# AD7190.net
KiCad netlist of a schematic drawn in Altium Designer
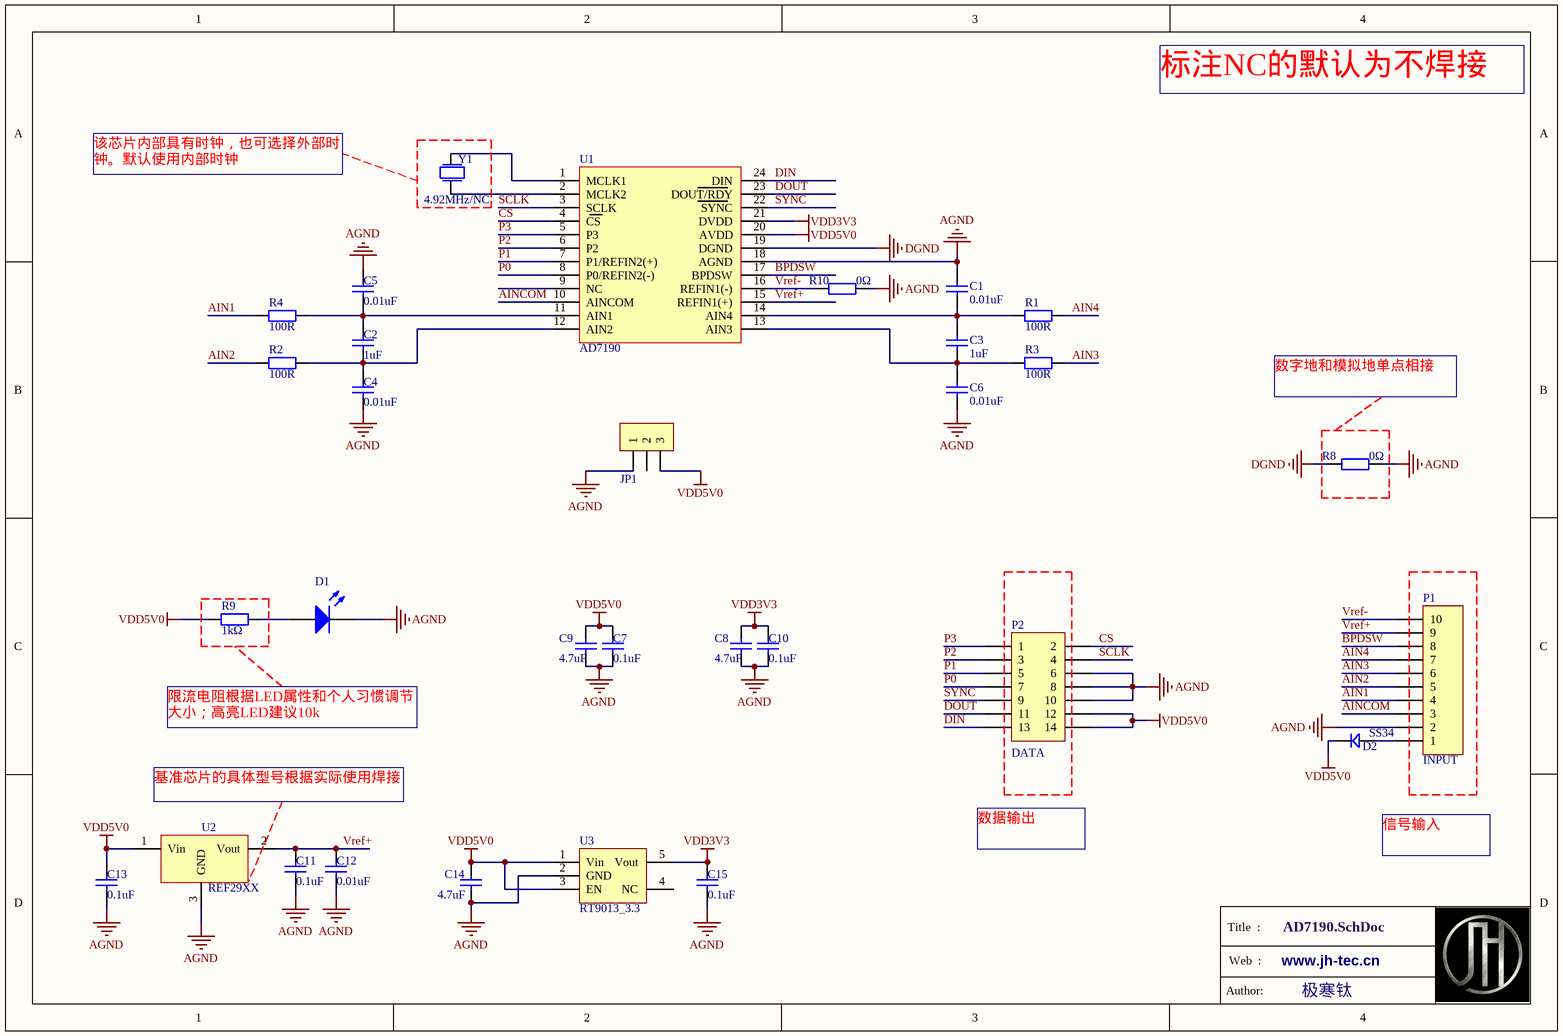
[diagram p0: AD7190.SchDoc]

(export (version "E")
  (design (tool "Eeschema 10.0.6"))
  (components
    (comp (ref "C1")
      (value "0.01uF")
      (footprint "JH_PCB:C0603")
      (description "Capacitor (Semiconductor SIM Model)")
      (fields (field (name "PUBLISHER") "Altium Limited"))
      (libsource (lib "mylib") (part "Cap Semi"))
    )
    (comp (ref "C2")
      (value "1uF")
      (footprint "JH_PCB:C0603")
      (description "Capacitor (Semiconductor SIM Model)")
      (fields (field (name "PUBLISHER") "Altium Limited"))
      (libsource (lib "mylib") (part "Cap Semi"))
    )
    (comp (ref "C3")
      (value "1uF")
      (footprint "JH_PCB:C0603")
      (description "Capacitor (Semiconductor SIM Model)")
      (fields (field (name "PUBLISHER") "Altium Limited"))
      (libsource (lib "mylib") (part "Cap Semi"))
    )
    (comp (ref "C4")
      (value "0.01uF")
      (footprint "JH_PCB:C0603")
      (description "Capacitor (Semiconductor SIM Model)")
      (fields (field (name "PUBLISHER") "Altium Limited"))
      (libsource (lib "mylib") (part "Cap Semi"))
    )
    (comp (ref "C5")
      (value "0.01uF")
      (footprint "JH_PCB:C0603")
      (description "Capacitor (Semiconductor SIM Model)")
      (fields (field (name "PUBLISHER") "Altium Limited"))
      (libsource (lib "mylib") (part "Cap Semi"))
    )
    (comp (ref "C6")
      (value "0.01uF")
      (footprint "JH_PCB:C0603")
      (description "Capacitor (Semiconductor SIM Model)")
      (fields (field (name "PUBLISHER") "Altium Limited"))
      (libsource (lib "mylib") (part "Cap Semi"))
    )
    (comp (ref "C7")
      (value "0.1uF")
      (footprint "JH_PCB:C0603")
      (description "Capacitor (Semiconductor SIM Model)")
      (fields (field (name "PUBLISHER") "Altium Limited"))
      (libsource (lib "mylib") (part "Cap Semi"))
    )
    (comp (ref "C8")
      (value "4.7uF")
      (footprint "JH_PCB:C0805")
      (description "Capacitor (Semiconductor SIM Model)")
      (fields (field (name "PUBLISHER") "Altium Limited"))
      (libsource (lib "mylib") (part "Cap Semi"))
    )
    (comp (ref "C9")
      (value "4.7uF")
      (footprint "JH_PCB:C0805")
      (description "Capacitor (Semiconductor SIM Model)")
      (fields (field (name "PUBLISHER") "Altium Limited"))
      (libsource (lib "mylib") (part "Cap Semi"))
    )
    (comp (ref "C10")
      (value "0.1uF")
      (footprint "JH_PCB:C0603")
      (description "Capacitor (Semiconductor SIM Model)")
      (fields (field (name "PUBLISHER") "Altium Limited"))
      (libsource (lib "mylib") (part "Cap Semi"))
    )
    (comp (ref "C11")
      (value "0.1uF")
      (footprint "JH_PCB:C0603")
      (description "Capacitor (Semiconductor SIM Model)")
      (fields (field (name "PUBLISHER") "Altium Limited"))
      (libsource (lib "mylib") (part "Cap Semi"))
    )
    (comp (ref "C12")
      (value "0.01uF")
      (footprint "JH_PCB:C0603")
      (description "Capacitor (Semiconductor SIM Model)")
      (fields (field (name "PUBLISHER") "Altium Limited"))
      (libsource (lib "mylib") (part "Cap Semi"))
    )
    (comp (ref "C13")
      (value "0.1uF")
      (footprint "JH_PCB:C0603")
      (description "Capacitor (Semiconductor SIM Model)")
      (fields (field (name "PUBLISHER") "Altium Limited"))
      (libsource (lib "mylib") (part "Cap Semi"))
    )
    (comp (ref "C14")
      (value "4.7uF")
      (footprint "JH_PCB:C0805")
      (description "Capacitor (Semiconductor SIM Model)")
      (fields (field (name "PUBLISHER") "Altium Limited"))
      (libsource (lib "mylib") (part "Cap Semi"))
    )
    (comp (ref "C15")
      (value "0.1uF")
      (footprint "JH_PCB:C0603")
      (description "Capacitor (Semiconductor SIM Model)")
      (fields (field (name "PUBLISHER") "Altium Limited"))
      (libsource (lib "mylib") (part "Cap Semi"))
    )
    (comp (ref "D1")
      (value "LED3")
      (footprint "JH_PCB:LED_GREEN_0603")
      (description "Typical BLUE SiC LED")
      (fields (field (name "PUBLISHER") "Altium Limited"))
      (libsource (lib "mylib") (part "LED3"))
    )
    (comp (ref "D2")
      (value "SS34")
      (footprint "JH_PCB:DO-214AC")
      (description "1N4148")
      (libsource (lib "ATK-SIM900A") (part "D"))
    )
    (comp (ref "JP1")
      (value "HDR-1X3")
      (footprint "XH2.54-WI-3P")
      (description "3P接插件")
      (libsource (lib "XH2.54") (part "Header 3"))
    )
    (comp (ref "P1")
      (value "INPUT")
      (footprint "JH_PCB:KF2EDGK-3.81-10P")
      (description "Header, 10-Pin")
      (fields (field (name "PUBLISHER") "Altium Limited"))
      (libsource (lib "Miscellaneous Connectors") (part "Header 10"))
    )
    (comp (ref "P2")
      (value "DATA")
      (footprint "JH_PCB:HDR2X7")
      (description "Header, 7-Pin, Dual row")
      (fields (field (name "PUBLISHER") "Altium Limited"))
      (libsource (lib "Miscellaneous Connectors") (part "Header 7X2"))
    )
    (comp (ref "R1")
      (value "100R")
      (footprint "JH_PCB:R0603")
      (description "Resistor")
      (fields (field (name "PUBLISHER") "Altium Limited"))
      (libsource (lib "Miscellaneous Devices") (part "Res2"))
    )
    (comp (ref "R2")
      (value "100R")
      (footprint "JH_PCB:R0603")
      (description "Resistor")
      (fields (field (name "PUBLISHER") "Altium Limited"))
      (libsource (lib "") (part "Res2_2"))
    )
    (comp (ref "R3")
      (value "100R")
      (footprint "JH_PCB:R0603")
      (description "Resistor")
      (fields (field (name "PUBLISHER") "Altium Limited"))
      (libsource (lib "Miscellaneous Devices") (part "Res2"))
    )
    (comp (ref "R4")
      (value "100R")
      (footprint "JH_PCB:R0603")
      (description "Resistor")
      (fields (field (name "PUBLISHER") "Altium Limited"))
      (libsource (lib "") (part "Res2_2"))
    )
    (comp (ref "R8")
      (value "0Ω")
      (footprint "JH_PCB:R0603")
      (description "Resistor")
      (fields (field (name "PUBLISHER") "Altium Limited"))
      (libsource (lib "") (part "Res2_1"))
    )
    (comp (ref "R9")
      (value "1kΩ")
      (footprint "JH_PCB:R0603")
      (description "Resistor")
      (fields (field (name "PUBLISHER") "Altium Limited"))
      (libsource (lib "") (part "Res2_1"))
    )
    (comp (ref "R10")
      (value "0Ω")
      (footprint "JH_PCB:R0603")
      (description "Resistor")
      (fields (field (name "PUBLISHER") "Altium Limited"))
      (libsource (lib "") (part "Res2_1"))
    )
    (comp (ref "U1") (value "AD7190") (footprint "JH_PCB:TSSOP24") (libsource (lib "常用sch") (part "AD7190")))
    (comp (ref "U2") (value "REF29XX") (libsource (lib "常用sch") (part "REF29XX")))
    (comp (ref "U3")
      (value "RT9013_3.3")
      (footprint "SOT23-5")
      (description "LDO")
      (libsource (lib "Black") (part "RT9013"))
    )
    (comp (ref "Y1")
      (value "4.92MHz/NC")
      (footprint "XTAL-HC49S")
      (description "MHz")
      (libsource (lib "常用sch") (part "XTAL"))
    )
  )
  (nets
    (net (code "1") (name "/AIN1") (class "Default")
      (node (ref "P1") (pin "4") (pinfunction "4_4") (pintype "passive"))
      (node (ref "R4") (pin "1") (pinfunction "1_1") (pintype "passive"))
    )
    (net (code "2") (name "/AIN2") (class "Default")
      (node (ref "P1") (pin "5") (pinfunction "5_5") (pintype "passive"))
      (node (ref "R2") (pin "1") (pinfunction "1_1") (pintype "passive"))
    )
    (net (code "3") (name "/AIN3") (class "Default")
      (node (ref "P1") (pin "6") (pinfunction "6_6") (pintype "passive"))
      (node (ref "R3") (pin "1") (pinfunction "1_1") (pintype "passive"))
    )
    (net (code "4") (name "/AIN4") (class "Default")
      (node (ref "P1") (pin "7") (pinfunction "7_7") (pintype "passive"))
      (node (ref "R1") (pin "1") (pinfunction "1_1") (pintype "passive"))
    )
    (net (code "5") (name "/AINCOM") (class "Default")
      (node (ref "P1") (pin "3") (pinfunction "3_3") (pintype "passive"))
      (node (ref "U1") (pin "10") (pinfunction "AINCOM_10") (pintype "passive"))
    )
    (net (code "6") (name "/BPDSW") (class "Default")
      (node (ref "P1") (pin "8") (pinfunction "8_8") (pintype "passive"))
      (node (ref "U1") (pin "17") (pinfunction "BPDSW_17") (pintype "passive"))
    )
    (net (code "7") (name "/CS") (class "Default")
      (node (ref "P2") (pin "2") (pinfunction "2_2") (pintype "passive"))
      (node (ref "U1") (pin "4") (pinfunction "CS_4") (pintype "passive"))
    )
    (net (code "8") (name "/DIN") (class "Default")
      (node (ref "P2") (pin "13") (pinfunction "13_13") (pintype "passive"))
      (node (ref "U1") (pin "24") (pinfunction "DIN_24") (pintype "passive"))
    )
    (net (code "9") (name "/DOUT") (class "Default")
      (node (ref "P2") (pin "11") (pinfunction "11_11") (pintype "passive"))
      (node (ref "U1") (pin "23") (pinfunction "DOUT/RDY_23") (pintype "passive"))
    )
    (net (code "10") (name "/P0") (class "Default")
      (node (ref "P2") (pin "7") (pinfunction "7_7") (pintype "passive"))
      (node (ref "U1") (pin "8") (pinfunction "P0/REFIN2(-)_8") (pintype "passive"))
    )
    (net (code "11") (name "/P1") (class "Default")
      (node (ref "P2") (pin "5") (pinfunction "5_5") (pintype "passive"))
      (node (ref "U1") (pin "7") (pinfunction "P1/REFIN2(+)_7") (pintype "passive"))
    )
    (net (code "12") (name "/P2") (class "Default")
      (node (ref "P2") (pin "3") (pinfunction "3_3") (pintype "passive"))
      (node (ref "U1") (pin "6") (pinfunction "P2_6") (pintype "passive"))
    )
    (net (code "13") (name "/P3") (class "Default")
      (node (ref "P2") (pin "1") (pinfunction "1_1") (pintype "passive"))
      (node (ref "U1") (pin "5") (pinfunction "P3_5") (pintype "passive"))
    )
    (net (code "14") (name "/SCLK") (class "Default")
      (node (ref "P2") (pin "4") (pinfunction "4_4") (pintype "passive"))
      (node (ref "U1") (pin "3") (pinfunction "SCLK_3") (pintype "passive"))
    )
    (net (code "15") (name "/SYNC") (class "Default")
      (node (ref "P2") (pin "9") (pinfunction "9_9") (pintype "passive"))
      (node (ref "U1") (pin "22") (pinfunction "SYNC_22") (pintype "passive"))
    )
    (net (code "16") (name "/Vref+") (class "Default")
      (node (ref "C11") (pin "1") (pinfunction "1_1") (pintype "passive"))
      (node (ref "C12") (pin "1") (pinfunction "1_1") (pintype "passive"))
      (node (ref "P1") (pin "9") (pinfunction "9_9") (pintype "passive"))
      (node (ref "U1") (pin "15") (pinfunction "REFIN1(+)_15") (pintype "passive"))
      (node (ref "U2") (pin "2") (pinfunction "Vout_2") (pintype "passive"))
    )
    (net (code "17") (name "/Vref-") (class "Default")
      (node (ref "P1") (pin "10") (pinfunction "10_10") (pintype "passive"))
      (node (ref "R10") (pin "2") (pinfunction "2_2") (pintype "passive"))
      (node (ref "U1") (pin "16") (pinfunction "REFIN1(-)_16") (pintype "passive"))
    )
    (net (code "18") (name "AGND") (class "Default")
      (node (ref "C1") (pin "1") (pinfunction "1_1") (pintype "passive"))
      (node (ref "C10") (pin "2") (pinfunction "2_2") (pintype "passive"))
      (node (ref "C11") (pin "2") (pinfunction "2_2") (pintype "passive"))
      (node (ref "C12") (pin "2") (pinfunction "2_2") (pintype "passive"))
      (node (ref "C13") (pin "2") (pinfunction "2_2") (pintype "passive"))
      (node (ref "C14") (pin "1") (pinfunction "1_1") (pintype "passive"))
      (node (ref "C15") (pin "2") (pinfunction "2_2") (pintype "passive"))
      (node (ref "C4") (pin "2") (pinfunction "2_2") (pintype "passive"))
      (node (ref "C5") (pin "1") (pinfunction "1_1") (pintype "passive"))
      (node (ref "C6") (pin "2") (pinfunction "2_2") (pintype "passive"))
      (node (ref "C7") (pin "2") (pinfunction "2_2") (pintype "passive"))
      (node (ref "C8") (pin "1") (pinfunction "1_1") (pintype "passive"))
      (node (ref "C9") (pin "1") (pinfunction "1_1") (pintype "passive"))
      (node (ref "D1") (pin "2") (pinfunction "K_2") (pintype "passive"))
      (node (ref "JP1") (pin "1") (pinfunction "1_1") (pintype "passive"))
      (node (ref "P1") (pin "2") (pinfunction "2_2") (pintype "passive"))
      (node (ref "P2") (pin "10") (pinfunction "10_10") (pintype "passive"))
      (node (ref "P2") (pin "6") (pinfunction "6_6") (pintype "passive"))
      (node (ref "P2") (pin "8") (pinfunction "8_8") (pintype "passive"))
      (node (ref "R10") (pin "1") (pinfunction "1_1") (pintype "passive"))
      (node (ref "R8") (pin "1") (pinfunction "1_1") (pintype "passive"))
      (node (ref "U1") (pin "18") (pinfunction "AGND_18") (pintype "passive"))
      (node (ref "U2") (pin "3") (pinfunction "GND_3") (pintype "passive"))
      (node (ref "U3") (pin "2") (pinfunction "GND_2") (pintype "passive"))
    )
    (net (code "19") (name "DGND") (class "Default")
      (node (ref "R8") (pin "2") (pinfunction "2_2") (pintype "passive"))
      (node (ref "U1") (pin "19") (pinfunction "DGND_19") (pintype "passive"))
    )
    (net (code "20") (name "Net-(D1-A)") (class "Default")
      (node (ref "D1") (pin "1") (pinfunction "A_1") (pintype "passive"))
      (node (ref "R9") (pin "1") (pinfunction "1_1") (pintype "passive"))
    )
    (net (code "21") (name "Net-(D2-Pad1)") (class "Default")
      (node (ref "D2") (pin "1") (pintype "passive"))
      (node (ref "P1") (pin "1") (pinfunction "1_1") (pintype "passive"))
    )
    (net (code "22") (name "Net-(U1-AIN1)") (class "Default")
      (node (ref "C2") (pin "1") (pinfunction "1_1") (pintype "passive"))
      (node (ref "C5") (pin "2") (pinfunction "2_2") (pintype "passive"))
      (node (ref "R4") (pin "2") (pinfunction "2_2") (pintype "passive"))
      (node (ref "U1") (pin "11") (pinfunction "AIN1_11") (pintype "passive"))
    )
    (net (code "23") (name "Net-(U1-AIN2)") (class "Default")
      (node (ref "C2") (pin "2") (pinfunction "2_2") (pintype "passive"))
      (node (ref "C4") (pin "1") (pinfunction "1_1") (pintype "passive"))
      (node (ref "R2") (pin "2") (pinfunction "2_2") (pintype "passive"))
      (node (ref "U1") (pin "12") (pinfunction "AIN2_12") (pintype "passive"))
    )
    (net (code "24") (name "Net-(U1-AIN3)") (class "Default")
      (node (ref "C3") (pin "2") (pinfunction "2_2") (pintype "passive"))
      (node (ref "C6") (pin "1") (pinfunction "1_1") (pintype "passive"))
      (node (ref "R3") (pin "2") (pinfunction "2_2") (pintype "passive"))
      (node (ref "U1") (pin "13") (pinfunction "AIN3_13") (pintype "passive"))
    )
    (net (code "25") (name "Net-(U1-AIN4)") (class "Default")
      (node (ref "C1") (pin "2") (pinfunction "2_2") (pintype "passive"))
      (node (ref "C3") (pin "1") (pinfunction "1_1") (pintype "passive"))
      (node (ref "R1") (pin "2") (pinfunction "2_2") (pintype "passive"))
      (node (ref "U1") (pin "14") (pinfunction "AIN4_14") (pintype "passive"))
    )
    (net (code "26") (name "Net-(U1-MCLK1)") (class "Default")
      (node (ref "U1") (pin "1") (pinfunction "MCLK1_1") (pintype "passive"))
      (node (ref "Y1") (pin "2") (pinfunction "2_2") (pintype "passive"))
    )
    (net (code "27") (name "Net-(U1-MCLK2)") (class "Default")
      (node (ref "U1") (pin "2") (pinfunction "MCLK2_2") (pintype "passive"))
      (node (ref "Y1") (pin "1") (pinfunction "1_1") (pintype "passive"))
    )
    (net (code "28") (name "VDD3V3") (class "Default")
      (node (ref "C10") (pin "1") (pinfunction "1_1") (pintype "passive"))
      (node (ref "C15") (pin "1") (pinfunction "1_1") (pintype "passive"))
      (node (ref "C8") (pin "2") (pinfunction "2_2") (pintype "passive"))
      (node (ref "U1") (pin "21") (pinfunction "DVDD_21") (pintype "passive"))
      (node (ref "U3") (pin "5") (pinfunction "Vout_5") (pintype "passive"))
    )
    (net (code "29") (name "VDD5V0") (class "Default")
      (node (ref "C13") (pin "1") (pinfunction "1_1") (pintype "passive"))
      (node (ref "C14") (pin "2") (pinfunction "2_2") (pintype "passive"))
      (node (ref "C7") (pin "1") (pinfunction "1_1") (pintype "passive"))
      (node (ref "C9") (pin "2") (pinfunction "2_2") (pintype "passive"))
      (node (ref "D2") (pin "2") (pintype "passive"))
      (node (ref "JP1") (pin "3") (pinfunction "3_3") (pintype "passive"))
      (node (ref "P2") (pin "12") (pinfunction "12_12") (pintype "passive"))
      (node (ref "P2") (pin "14") (pinfunction "14_14") (pintype "passive"))
      (node (ref "R9") (pin "2") (pinfunction "2_2") (pintype "passive"))
      (node (ref "U1") (pin "20") (pinfunction "AVDD_20") (pintype "passive"))
      (node (ref "U2") (pin "1") (pinfunction "Vin_1") (pintype "passive"))
      (node (ref "U3") (pin "1") (pinfunction "Vin_1") (pintype "passive"))
      (node (ref "U3") (pin "3") (pinfunction "EN_3") (pintype "passive"))
    )
    (net (code "30") (name "unconnected-(JP1-Pad2)") (class "Default")
      (node (ref "JP1") (pin "2") (pinfunction "2_2") (pintype "passive"))
    )
    (net (code "31") (name "unconnected-(U1-NC-Pad9)") (class "Default")
      (node (ref "U1") (pin "9") (pinfunction "NC_9") (pintype "passive"))
    )
    (net (code "32") (name "unconnected-(U3-NC-Pad4)") (class "Default")
      (node (ref "U3") (pin "4") (pinfunction "NC_4") (pintype "passive"))
    )
  )
)
